# hextech-mechahand.net
KiCad netlist of a schematic drawn in EasyEDA
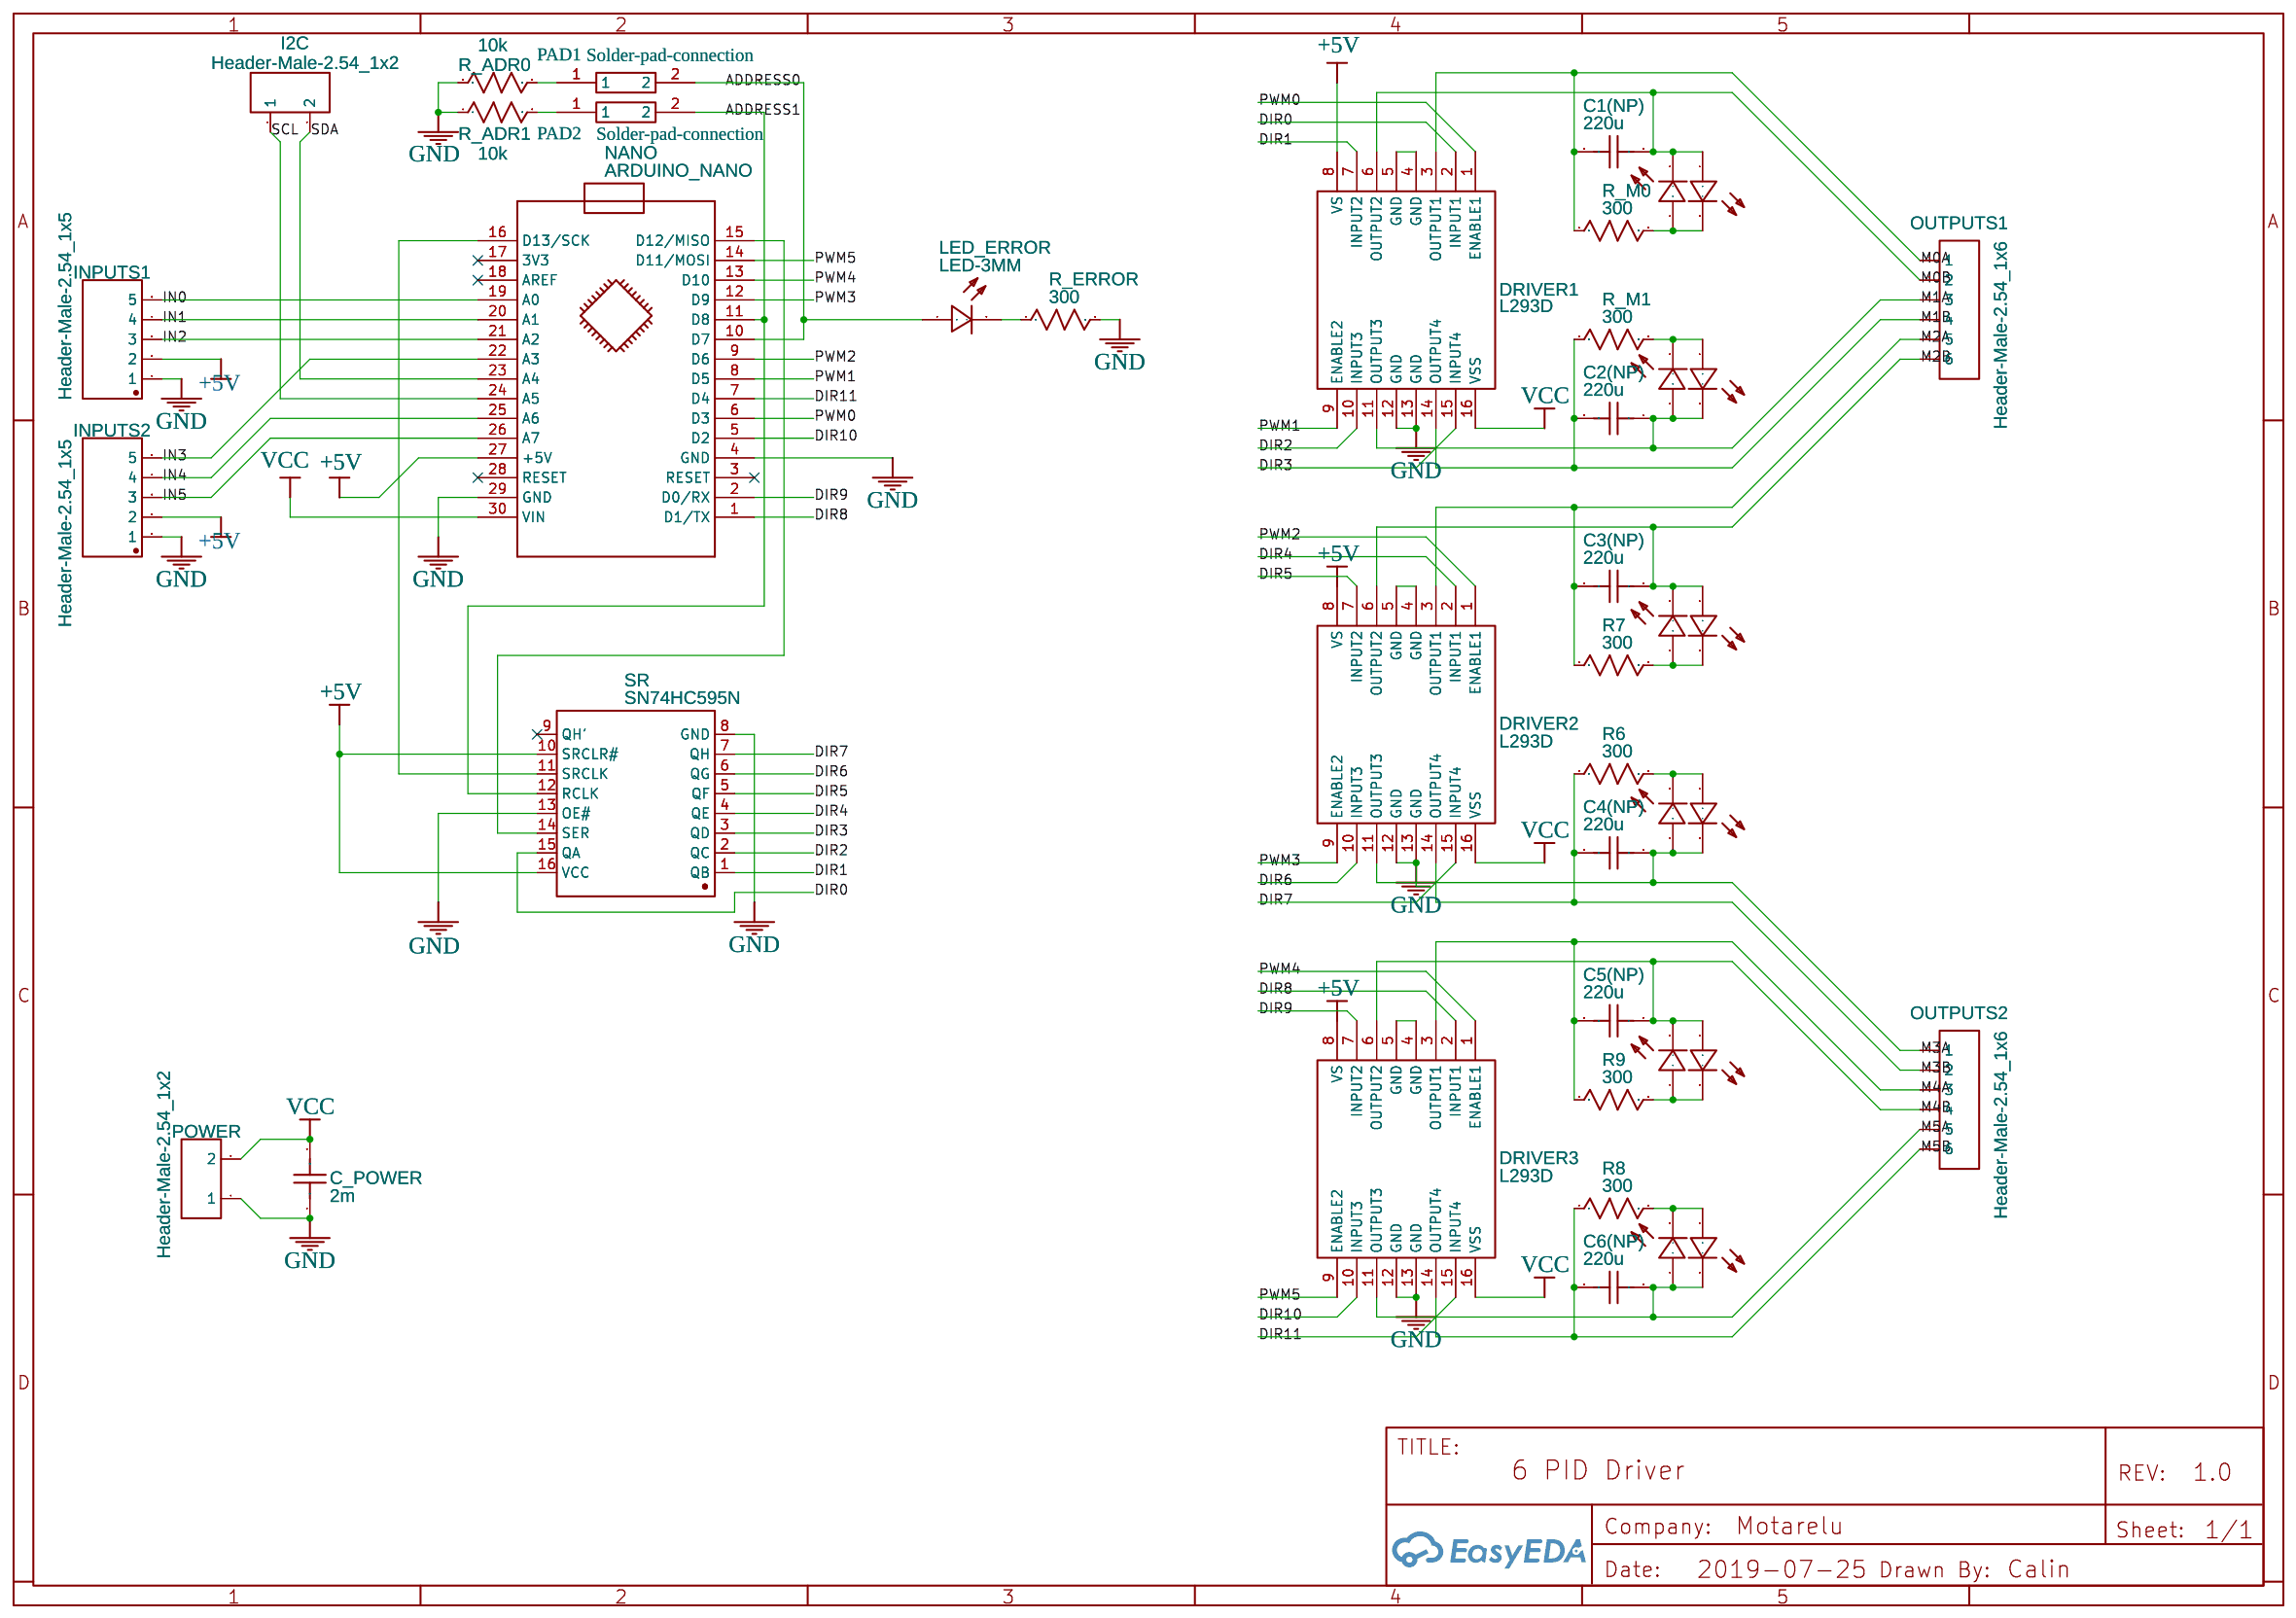
[diagram p0: schematic sheet]

(export (version "E")
  (design (tool "Eeschema 10.0.6"))
  (components
    (comp (ref "C1(NP)")
      (value "220u")
      (fields (field (name "BOM_Manufacturer Part") "?"))
      (libsource (lib "") (part "Cap_RAD-0.1_US_3"))
    )
    (comp (ref "C2(NP)")
      (value "220u")
      (fields (field (name "BOM_Manufacturer Part") "?"))
      (libsource (lib "") (part "Cap_RAD-0.1_US_5"))
    )
    (comp (ref "C3(NP)")
      (value "220u")
      (fields (field (name "BOM_Manufacturer Part") "?"))
      (libsource (lib "") (part "Cap_RAD-0.1_US"))
    )
    (comp (ref "C4(NP)")
      (value "220u")
      (fields (field (name "BOM_Manufacturer Part") "?"))
      (libsource (lib "") (part "Cap_RAD-0.1_US_2"))
    )
    (comp (ref "C5(NP)")
      (value "220u")
      (fields (field (name "BOM_Manufacturer Part") "?"))
      (libsource (lib "") (part "Cap_RAD-0.1_US_1"))
    )
    (comp (ref "C6(NP)")
      (value "220u")
      (fields (field (name "BOM_Manufacturer Part") "?"))
      (libsource (lib "") (part "Cap_RAD-0.1_US_6"))
    )
    (comp (ref "C_POWER")
      (value "2m")
      (fields (field (name "BOM_Manufacturer Part") "?"))
      (libsource (lib "") (part "Cap_RAD-0.1_US_4"))
    )
    (comp (ref "DRIVER1")
      (value "L293D")
      (fields (field (name "BOM_Supplier Part") "C12340"))
      (libsource (lib "") (part "Unknown_700_140"))
    )
    (comp (ref "DRIVER2")
      (value "L293D")
      (fields (field (name "BOM_Supplier Part") "C12340"))
      (libsource (lib "") (part "Unknown_700_360"))
    )
    (comp (ref "DRIVER3")
      (value "L293D")
      (fields (field (name "BOM_Supplier Part") "C12340"))
      (libsource (lib "") (part "Unknown_700_580"))
    )
    (comp (ref "I2C")
      (value "Header-Male-2.54_1x2")
      (fields (field (name "BOM_Manufacturer Part") "826629-2") (field (name "BOM_Supplier Part") "C86471"))
      (libsource (lib "") (part "Unknown_140_45"))
    )
    (comp (ref "INPUTS1")
      (value "Header-Male-2.54_1x5")
      (fields
        (field (name "BOM_Manufacturer Part") "210S-1*5P L=11.6MMGold-plated black")
        (field (name "BOM_Supplier Part") "C124379")
      )
      (libsource (lib "") (part "Unknown_55_165"))
    )
    (comp (ref "INPUTS2")
      (value "Header-Male-2.54_1x5")
      (fields
        (field (name "BOM_Manufacturer Part") "210S-1*5P L=11.6MMGold-plated black")
        (field (name "BOM_Supplier Part") "C124379")
      )
      (libsource (lib "") (part "Unknown_55_245"))
    )
    (comp (ref "LED_ERROR")
      (value "LED-3MM")
      (fields
        (field (name "BOM_Manufacturer Part") "204-10SURD/S530-A3")
        (field (name "BOM_Supplier Part") "C99772")
      )
      (libsource (lib "") (part "Unknown_480_150"))
    )
    (comp (ref "LED_M0A")
      (value "LED-3MM")
      (fields
        (field (name "BOM_Manufacturer Part") "204-10SURD/S530-A3")
        (field (name "BOM_Supplier Part") "C99772")
      )
      (libsource (lib "") (part "Unknown_835_90"))
    )
    (comp (ref "LED_M0B")
      (value "LED-3MM")
      (fields
        (field (name "BOM_Manufacturer Part") "204-10SURD/S530-A3")
        (field (name "BOM_Supplier Part") "C99772")
      )
      (libsource (lib "") (part "Unknown_860_90"))
    )
    (comp (ref "LED_M1A")
      (value "LED-3MM")
      (fields
        (field (name "BOM_Manufacturer Part") "204-10SURD/S530-A3")
        (field (name "BOM_Supplier Part") "C99772")
      )
      (libsource (lib "") (part "Unknown_835_185"))
    )
    (comp (ref "LED_M1B")
      (value "LED-3MM")
      (fields
        (field (name "BOM_Manufacturer Part") "204-10SURD/S530-A3")
        (field (name "BOM_Supplier Part") "C99772")
      )
      (libsource (lib "") (part "Unknown_860_185"))
    )
    (comp (ref "LED_M2A")
      (value "LED-3MM")
      (fields
        (field (name "BOM_Manufacturer Part") "204-10SURD/S530-A3")
        (field (name "BOM_Supplier Part") "C99772")
      )
      (libsource (lib "") (part "Unknown_835_310"))
    )
    (comp (ref "LED_M2B")
      (value "LED-3MM")
      (fields
        (field (name "BOM_Manufacturer Part") "204-10SURD/S530-A3")
        (field (name "BOM_Supplier Part") "C99772")
      )
      (libsource (lib "") (part "Unknown_860_310"))
    )
    (comp (ref "LED_M3A")
      (value "LED-3MM")
      (fields
        (field (name "BOM_Manufacturer Part") "204-10SURD/S530-A3")
        (field (name "BOM_Supplier Part") "C99772")
      )
      (libsource (lib "") (part "Unknown_835_405"))
    )
    (comp (ref "LED_M3B")
      (value "LED-3MM")
      (fields
        (field (name "BOM_Manufacturer Part") "204-10SURD/S530-A3")
        (field (name "BOM_Supplier Part") "C99772")
      )
      (libsource (lib "") (part "Unknown_860_405"))
    )
    (comp (ref "LED_M4A")
      (value "LED-3MM")
      (fields
        (field (name "BOM_Manufacturer Part") "204-10SURD/S530-A3")
        (field (name "BOM_Supplier Part") "C99772")
      )
      (libsource (lib "") (part "Unknown_835_530"))
    )
    (comp (ref "LED_M4B")
      (value "LED-3MM")
      (fields
        (field (name "BOM_Manufacturer Part") "204-10SURD/S530-A3")
        (field (name "BOM_Supplier Part") "C99772")
      )
      (libsource (lib "") (part "Unknown_860_530"))
    )
    (comp (ref "LED_M5A")
      (value "LED-3MM")
      (fields
        (field (name "BOM_Manufacturer Part") "204-10SURD/S530-A3")
        (field (name "BOM_Supplier Part") "C99772")
      )
      (libsource (lib "") (part "Unknown_835_625"))
    )
    (comp (ref "LED_M5B")
      (value "LED-3MM")
      (fields
        (field (name "BOM_Manufacturer Part") "204-10SURD/S530-A3")
        (field (name "BOM_Supplier Part") "C99772")
      )
      (libsource (lib "") (part "Unknown_860_625"))
    )
    (comp (ref "NANO")
      (value "ARDUINO_NANO")
      (fields (field (name "BOM_Manufacturer Part") "?"))
      (libsource (lib "") (part "Unknown_305_180"))
    )
    (comp (ref "OUTPUTS1")
      (value "Header-Male-2.54_1x6")
      (fields (field (name "BOM_Supplier Part") "C37208"))
      (libsource (lib "") (part "Unknown_980_150"))
    )
    (comp (ref "OUTPUTS2")
      (value "Header-Male-2.54_1x6")
      (fields (field (name "BOM_Supplier Part") "C37208"))
      (libsource (lib "") (part "Unknown_980_550"))
    )
    (comp (ref "PAD1") (value "Solder-pad-connection") (libsource (lib "") (part "Unknown_310_30")))
    (comp (ref "PAD2") (value "Solder-pad-connection") (libsource (lib "") (part "Unknown_310_45")))
    (comp (ref "POWER")
      (value "Header-Male-2.54_1x2")
      (fields (field (name "BOM_Manufacturer Part") "826629-2") (field (name "BOM_Supplier Part") "C86471"))
      (libsource (lib "") (part "Unknown_100_590"))
    )
    (comp (ref "R6")
      (value "300")
      (fields (field (name "BOM_Manufacturer Part") "?"))
      (libsource (lib "") (part "Res_AXIAL-0.3(1/8W)_US"))
    )
    (comp (ref "R7")
      (value "300")
      (fields (field (name "BOM_Manufacturer Part") "?"))
      (libsource (lib "") (part "Res_AXIAL-0.3(1/8W)_US"))
    )
    (comp (ref "R8")
      (value "300")
      (fields (field (name "BOM_Manufacturer Part") "?"))
      (libsource (lib "") (part "Res_AXIAL-0.3(1/8W)_US"))
    )
    (comp (ref "R9")
      (value "300")
      (fields (field (name "BOM_Manufacturer Part") "?"))
      (libsource (lib "") (part "Res_AXIAL-0.3(1/8W)_US"))
    )
    (comp (ref "R_ADR0")
      (value "10k")
      (fields (field (name "BOM_Manufacturer Part") "?"))
      (libsource (lib "") (part "Res_AXIAL-0.3(1/8W)_US_3"))
    )
    (comp (ref "R_ADR1")
      (value "10k")
      (fields (field (name "BOM_Manufacturer Part") "?"))
      (libsource (lib "") (part "Res_AXIAL-0.3(1/8W)_US_3"))
    )
    (comp (ref "R_ERROR")
      (value "300")
      (fields (field (name "BOM_Manufacturer Part") "?"))
      (libsource (lib "") (part "Res_AXIAL-0.3(1/8W)_US_1"))
    )
    (comp (ref "R_M0")
      (value "300")
      (fields (field (name "BOM_Manufacturer Part") "?"))
      (libsource (lib "") (part "Res_AXIAL-0.3(1/8W)_US_2"))
    )
    (comp (ref "R_M1")
      (value "300")
      (fields (field (name "BOM_Manufacturer Part") "?"))
      (libsource (lib "") (part "Res_AXIAL-0.3(1/8W)_US_2"))
    )
    (comp (ref "SR")
      (value "SN74HC595N")
      (fields (field (name "BOM_Supplier Part") "C78711"))
      (libsource (lib "") (part "Unknown_315_400"))
    )
  )
  (nets
    (net (code "1") (name "+5V") (class "Default")
      (node (ref "DRIVER1") (pin "8") (pinfunction "VS_8") (pintype "unspecified"))
      (node (ref "DRIVER2") (pin "8") (pinfunction "VS_8") (pintype "unspecified"))
      (node (ref "DRIVER3") (pin "8") (pinfunction "VS_8") (pintype "unspecified"))
      (node (ref "INPUTS1") (pin "2") (pinfunction "2_2") (pintype "unspecified"))
      (node (ref "INPUTS2") (pin "2") (pinfunction "2_2") (pintype "unspecified"))
      (node (ref "NANO") (pin "27") (pinfunction "+5V_27") (pintype "unspecified"))
      (node (ref "SR") (pin "10") (pinfunction "SRCLR#_10") (pintype "unspecified"))
      (node (ref "SR") (pin "16") (pinfunction "VCC_16") (pintype "unspecified"))
    )
    (net (code "2") (name "/ADDRESS0") (class "Default")
      (node (ref "LED_ERROR") (pin "1") (pinfunction "+_1") (pintype "unspecified"))
      (node (ref "NANO") (pin "10") (pinfunction "D7_10") (pintype "unspecified"))
      (node (ref "PAD1") (pin "2") (pinfunction "2_2") (pintype "unspecified"))
    )
    (net (code "3") (name "/ADDRESS1") (class "Default")
      (node (ref "NANO") (pin "11") (pinfunction "D8_11") (pintype "unspecified"))
      (node (ref "PAD2") (pin "2") (pinfunction "2_2") (pintype "unspecified"))
      (node (ref "SR") (pin "12") (pinfunction "RCLK_12") (pintype "unspecified"))
    )
    (net (code "4") (name "/DIR0") (class "Default")
      (node (ref "DRIVER1") (pin "2") (pinfunction "INPUT1_2") (pintype "unspecified"))
      (node (ref "SR") (pin "15") (pinfunction "QA_15") (pintype "unspecified"))
    )
    (net (code "5") (name "/DIR1") (class "Default")
      (node (ref "DRIVER1") (pin "7") (pinfunction "INPUT2_7") (pintype "unspecified"))
      (node (ref "SR") (pin "1") (pinfunction "QB_1") (pintype "unspecified"))
    )
    (net (code "6") (name "/DIR2") (class "Default")
      (node (ref "DRIVER1") (pin "10") (pinfunction "INPUT3_10") (pintype "unspecified"))
      (node (ref "SR") (pin "2") (pinfunction "QC_2") (pintype "unspecified"))
    )
    (net (code "7") (name "/DIR3") (class "Default")
      (node (ref "DRIVER1") (pin "15") (pinfunction "INPUT4_15") (pintype "unspecified"))
      (node (ref "SR") (pin "3") (pinfunction "QD_3") (pintype "unspecified"))
    )
    (net (code "8") (name "/DIR4") (class "Default")
      (node (ref "DRIVER2") (pin "2") (pinfunction "INPUT1_2") (pintype "unspecified"))
      (node (ref "SR") (pin "4") (pinfunction "QE_4") (pintype "unspecified"))
    )
    (net (code "9") (name "/DIR5") (class "Default")
      (node (ref "DRIVER2") (pin "7") (pinfunction "INPUT2_7") (pintype "unspecified"))
      (node (ref "SR") (pin "5") (pinfunction "QF_5") (pintype "unspecified"))
    )
    (net (code "10") (name "/DIR6") (class "Default")
      (node (ref "DRIVER2") (pin "10") (pinfunction "INPUT3_10") (pintype "unspecified"))
      (node (ref "SR") (pin "6") (pinfunction "QG_6") (pintype "unspecified"))
    )
    (net (code "11") (name "/DIR7") (class "Default")
      (node (ref "DRIVER2") (pin "15") (pinfunction "INPUT4_15") (pintype "unspecified"))
      (node (ref "SR") (pin "7") (pinfunction "QH_7") (pintype "unspecified"))
    )
    (net (code "12") (name "/DIR8") (class "Default")
      (node (ref "DRIVER3") (pin "2") (pinfunction "INPUT1_2") (pintype "unspecified"))
      (node (ref "NANO") (pin "1") (pinfunction "D1/TX_1") (pintype "unspecified"))
    )
    (net (code "13") (name "/DIR9") (class "Default")
      (node (ref "DRIVER3") (pin "7") (pinfunction "INPUT2_7") (pintype "unspecified"))
      (node (ref "NANO") (pin "2") (pinfunction "D0/RX_2") (pintype "unspecified"))
    )
    (net (code "14") (name "/DIR10") (class "Default")
      (node (ref "DRIVER3") (pin "10") (pinfunction "INPUT3_10") (pintype "unspecified"))
      (node (ref "NANO") (pin "5") (pinfunction "D2_5") (pintype "unspecified"))
    )
    (net (code "15") (name "/DIR11") (class "Default")
      (node (ref "DRIVER3") (pin "15") (pinfunction "INPUT4_15") (pintype "unspecified"))
      (node (ref "NANO") (pin "7") (pinfunction "D4_7") (pintype "unspecified"))
    )
    (net (code "16") (name "/IN0") (class "Default")
      (node (ref "INPUTS1") (pin "5") (pinfunction "5_5") (pintype "unspecified"))
      (node (ref "NANO") (pin "19") (pinfunction "A0_19") (pintype "unspecified"))
    )
    (net (code "17") (name "/IN1") (class "Default")
      (node (ref "INPUTS1") (pin "4") (pinfunction "4_4") (pintype "unspecified"))
      (node (ref "NANO") (pin "20") (pinfunction "A1_20") (pintype "unspecified"))
    )
    (net (code "18") (name "/IN2") (class "Default")
      (node (ref "INPUTS1") (pin "3") (pinfunction "3_3") (pintype "unspecified"))
      (node (ref "NANO") (pin "21") (pinfunction "A2_21") (pintype "unspecified"))
    )
    (net (code "19") (name "/IN3") (class "Default")
      (node (ref "INPUTS2") (pin "5") (pinfunction "5_5") (pintype "unspecified"))
      (node (ref "NANO") (pin "22") (pinfunction "A3_22") (pintype "unspecified"))
    )
    (net (code "20") (name "/IN4") (class "Default")
      (node (ref "INPUTS2") (pin "4") (pinfunction "4_4") (pintype "unspecified"))
      (node (ref "NANO") (pin "25") (pinfunction "A6_25") (pintype "unspecified"))
    )
    (net (code "21") (name "/IN5") (class "Default")
      (node (ref "INPUTS2") (pin "3") (pinfunction "3_3") (pintype "unspecified"))
      (node (ref "NANO") (pin "26") (pinfunction "A7_26") (pintype "unspecified"))
    )
    (net (code "22") (name "/M0A") (class "Default")
      (node (ref "C1(NP)") (pin "2") (pinfunction "2_2") (pintype "unspecified"))
      (node (ref "DRIVER1") (pin "3") (pinfunction "OUTPUT1_3") (pintype "unspecified"))
      (node (ref "OUTPUTS1") (pin "1") (pinfunction "1_1") (pintype "input"))
      (node (ref "R_M0") (pin "1") (pinfunction "1_1") (pintype "unspecified"))
    )
    (net (code "23") (name "/M0B") (class "Default")
      (node (ref "C1(NP)") (pin "1") (pinfunction "1_1") (pintype "unspecified"))
      (node (ref "DRIVER1") (pin "6") (pinfunction "OUTPUT2_6") (pintype "unspecified"))
      (node (ref "LED_M0A") (pin "2") (pinfunction "-_2") (pintype "unspecified"))
      (node (ref "LED_M0B") (pin "1") (pinfunction "+_1") (pintype "unspecified"))
      (node (ref "OUTPUTS1") (pin "2") (pinfunction "2_2") (pintype "input"))
    )
    (net (code "24") (name "/M1A") (class "Default")
      (node (ref "C2(NP)") (pin "1") (pinfunction "1_1") (pintype "unspecified"))
      (node (ref "DRIVER1") (pin "11") (pinfunction "OUTPUT3_11") (pintype "unspecified"))
      (node (ref "LED_M1A") (pin "1") (pinfunction "+_1") (pintype "unspecified"))
      (node (ref "LED_M1B") (pin "2") (pinfunction "-_2") (pintype "unspecified"))
      (node (ref "OUTPUTS1") (pin "3") (pinfunction "3_3") (pintype "input"))
    )
    (net (code "25") (name "/M1B") (class "Default")
      (node (ref "C2(NP)") (pin "2") (pinfunction "2_2") (pintype "unspecified"))
      (node (ref "DRIVER1") (pin "14") (pinfunction "OUTPUT4_14") (pintype "unspecified"))
      (node (ref "OUTPUTS1") (pin "4") (pinfunction "4_4") (pintype "input"))
      (node (ref "R_M1") (pin "1") (pinfunction "1_1") (pintype "unspecified"))
    )
    (net (code "26") (name "/M2A") (class "Default")
      (node (ref "C3(NP)") (pin "2") (pinfunction "2_2") (pintype "unspecified"))
      (node (ref "DRIVER2") (pin "3") (pinfunction "OUTPUT1_3") (pintype "unspecified"))
      (node (ref "OUTPUTS1") (pin "5") (pinfunction "5_5") (pintype "input"))
      (node (ref "R7") (pin "1") (pinfunction "1_1") (pintype "unspecified"))
    )
    (net (code "27") (name "/M2B") (class "Default")
      (node (ref "C3(NP)") (pin "1") (pinfunction "1_1") (pintype "unspecified"))
      (node (ref "DRIVER2") (pin "6") (pinfunction "OUTPUT2_6") (pintype "unspecified"))
      (node (ref "LED_M2A") (pin "2") (pinfunction "-_2") (pintype "unspecified"))
      (node (ref "LED_M2B") (pin "1") (pinfunction "+_1") (pintype "unspecified"))
      (node (ref "OUTPUTS1") (pin "6") (pinfunction "6_6") (pintype "input"))
    )
    (net (code "28") (name "/M3A") (class "Default")
      (node (ref "C4(NP)") (pin "1") (pinfunction "1_1") (pintype "unspecified"))
      (node (ref "DRIVER2") (pin "11") (pinfunction "OUTPUT3_11") (pintype "unspecified"))
      (node (ref "LED_M3A") (pin "1") (pinfunction "+_1") (pintype "unspecified"))
      (node (ref "LED_M3B") (pin "2") (pinfunction "-_2") (pintype "unspecified"))
      (node (ref "OUTPUTS2") (pin "1") (pinfunction "1_1") (pintype "input"))
    )
    (net (code "29") (name "/M3B") (class "Default")
      (node (ref "C4(NP)") (pin "2") (pinfunction "2_2") (pintype "unspecified"))
      (node (ref "DRIVER2") (pin "14") (pinfunction "OUTPUT4_14") (pintype "unspecified"))
      (node (ref "OUTPUTS2") (pin "2") (pinfunction "2_2") (pintype "input"))
      (node (ref "R6") (pin "1") (pinfunction "1_1") (pintype "unspecified"))
    )
    (net (code "30") (name "/M4A") (class "Default")
      (node (ref "C5(NP)") (pin "2") (pinfunction "2_2") (pintype "unspecified"))
      (node (ref "DRIVER3") (pin "3") (pinfunction "OUTPUT1_3") (pintype "unspecified"))
      (node (ref "OUTPUTS2") (pin "3") (pinfunction "3_3") (pintype "input"))
      (node (ref "R9") (pin "1") (pinfunction "1_1") (pintype "unspecified"))
    )
    (net (code "31") (name "/M4B") (class "Default")
      (node (ref "C5(NP)") (pin "1") (pinfunction "1_1") (pintype "unspecified"))
      (node (ref "DRIVER3") (pin "6") (pinfunction "OUTPUT2_6") (pintype "unspecified"))
      (node (ref "LED_M4A") (pin "2") (pinfunction "-_2") (pintype "unspecified"))
      (node (ref "LED_M4B") (pin "1") (pinfunction "+_1") (pintype "unspecified"))
      (node (ref "OUTPUTS2") (pin "4") (pinfunction "4_4") (pintype "input"))
    )
    (net (code "32") (name "/M5A") (class "Default")
      (node (ref "C6(NP)") (pin "1") (pinfunction "1_1") (pintype "unspecified"))
      (node (ref "DRIVER3") (pin "11") (pinfunction "OUTPUT3_11") (pintype "unspecified"))
      (node (ref "LED_M5A") (pin "1") (pinfunction "+_1") (pintype "unspecified"))
      (node (ref "LED_M5B") (pin "2") (pinfunction "-_2") (pintype "unspecified"))
      (node (ref "OUTPUTS2") (pin "5") (pinfunction "5_5") (pintype "input"))
    )
    (net (code "33") (name "/M5B") (class "Default")
      (node (ref "C6(NP)") (pin "2") (pinfunction "2_2") (pintype "unspecified"))
      (node (ref "DRIVER3") (pin "14") (pinfunction "OUTPUT4_14") (pintype "unspecified"))
      (node (ref "OUTPUTS2") (pin "6") (pinfunction "6_6") (pintype "input"))
      (node (ref "R8") (pin "1") (pinfunction "1_1") (pintype "unspecified"))
    )
    (net (code "34") (name "/PWM0") (class "Default")
      (node (ref "DRIVER1") (pin "1") (pinfunction "ENABLE1_1") (pintype "unspecified"))
      (node (ref "NANO") (pin "6") (pinfunction "D3_6") (pintype "unspecified"))
    )
    (net (code "35") (name "/PWM1") (class "Default")
      (node (ref "DRIVER1") (pin "9") (pinfunction "ENABLE2_9") (pintype "unspecified"))
      (node (ref "NANO") (pin "8") (pinfunction "D5_8") (pintype "unspecified"))
    )
    (net (code "36") (name "/PWM2") (class "Default")
      (node (ref "DRIVER2") (pin "1") (pinfunction "ENABLE1_1") (pintype "unspecified"))
      (node (ref "NANO") (pin "9") (pinfunction "D6_9") (pintype "unspecified"))
    )
    (net (code "37") (name "/PWM3") (class "Default")
      (node (ref "DRIVER2") (pin "9") (pinfunction "ENABLE2_9") (pintype "unspecified"))
      (node (ref "NANO") (pin "12") (pinfunction "D9_12") (pintype "unspecified"))
    )
    (net (code "38") (name "/PWM4") (class "Default")
      (node (ref "DRIVER3") (pin "1") (pinfunction "ENABLE1_1") (pintype "unspecified"))
      (node (ref "NANO") (pin "13") (pinfunction "D10_13") (pintype "unspecified"))
    )
    (net (code "39") (name "/PWM5") (class "Default")
      (node (ref "DRIVER3") (pin "9") (pinfunction "ENABLE2_9") (pintype "unspecified"))
      (node (ref "NANO") (pin "14") (pinfunction "D11/MOSI_14") (pintype "unspecified"))
    )
    (net (code "40") (name "/SCL") (class "Default")
      (node (ref "I2C") (pin "1") (pinfunction "1_1") (pintype "unspecified"))
      (node (ref "NANO") (pin "24") (pinfunction "A5_24") (pintype "unspecified"))
    )
    (net (code "41") (name "/SDA") (class "Default")
      (node (ref "I2C") (pin "2") (pinfunction "2_2") (pintype "unspecified"))
      (node (ref "NANO") (pin "23") (pinfunction "A4_23") (pintype "unspecified"))
    )
    (net (code "42") (name "GND") (class "Default")
      (node (ref "C_POWER") (pin "1") (pinfunction "1_1") (pintype "unspecified"))
      (node (ref "DRIVER1") (pin "12") (pinfunction "GND_12") (pintype "unspecified"))
      (node (ref "DRIVER1") (pin "13") (pinfunction "GND_13") (pintype "unspecified"))
      (node (ref "DRIVER2") (pin "12") (pinfunction "GND_12") (pintype "unspecified"))
      (node (ref "DRIVER2") (pin "13") (pinfunction "GND_13") (pintype "unspecified"))
      (node (ref "DRIVER3") (pin "12") (pinfunction "GND_12") (pintype "unspecified"))
      (node (ref "DRIVER3") (pin "13") (pinfunction "GND_13") (pintype "unspecified"))
      (node (ref "INPUTS1") (pin "1") (pinfunction "1_1") (pintype "unspecified"))
      (node (ref "INPUTS2") (pin "1") (pinfunction "1_1") (pintype "unspecified"))
      (node (ref "NANO") (pin "29") (pinfunction "GND_29") (pintype "unspecified"))
      (node (ref "NANO") (pin "4") (pinfunction "GND_4") (pintype "unspecified"))
      (node (ref "POWER") (pin "1") (pinfunction "1_1") (pintype "unspecified"))
      (node (ref "R_ADR0") (pin "1") (pinfunction "1_1") (pintype "unspecified"))
      (node (ref "R_ADR1") (pin "1") (pinfunction "1_1") (pintype "unspecified"))
      (node (ref "R_ERROR") (pin "2") (pinfunction "2_2") (pintype "unspecified"))
      (node (ref "SR") (pin "13") (pinfunction "OE#_13") (pintype "unspecified"))
      (node (ref "SR") (pin "8") (pinfunction "GND_8") (pintype "unspecified"))
    )
    (net (code "43") (name "Net-(DRIVER1-GND-Pad4)") (class "Default")
      (node (ref "DRIVER1") (pin "4") (pinfunction "GND_4") (pintype "unspecified"))
      (node (ref "DRIVER1") (pin "5") (pinfunction "GND_5") (pintype "unspecified"))
    )
    (net (code "44") (name "Net-(DRIVER2-GND-Pad4)") (class "Default")
      (node (ref "DRIVER2") (pin "4") (pinfunction "GND_4") (pintype "unspecified"))
      (node (ref "DRIVER2") (pin "5") (pinfunction "GND_5") (pintype "unspecified"))
    )
    (net (code "45") (name "Net-(DRIVER3-GND-Pad4)") (class "Default")
      (node (ref "DRIVER3") (pin "4") (pinfunction "GND_4") (pintype "unspecified"))
      (node (ref "DRIVER3") (pin "5") (pinfunction "GND_5") (pintype "unspecified"))
    )
    (net (code "46") (name "Net-(LED_ERROR--)") (class "Default")
      (node (ref "LED_ERROR") (pin "2") (pinfunction "-_2") (pintype "unspecified"))
      (node (ref "R_ERROR") (pin "1") (pinfunction "1_1") (pintype "unspecified"))
    )
    (net (code "47") (name "Net-(LED_M0A-+)") (class "Default")
      (node (ref "LED_M0A") (pin "1") (pinfunction "+_1") (pintype "unspecified"))
      (node (ref "LED_M0B") (pin "2") (pinfunction "-_2") (pintype "unspecified"))
      (node (ref "R_M0") (pin "2") (pinfunction "2_2") (pintype "unspecified"))
    )
    (net (code "48") (name "Net-(LED_M1A--)") (class "Default")
      (node (ref "LED_M1A") (pin "2") (pinfunction "-_2") (pintype "unspecified"))
      (node (ref "LED_M1B") (pin "1") (pinfunction "+_1") (pintype "unspecified"))
      (node (ref "R_M1") (pin "2") (pinfunction "2_2") (pintype "unspecified"))
    )
    (net (code "49") (name "Net-(LED_M2A-+)") (class "Default")
      (node (ref "LED_M2A") (pin "1") (pinfunction "+_1") (pintype "unspecified"))
      (node (ref "LED_M2B") (pin "2") (pinfunction "-_2") (pintype "unspecified"))
      (node (ref "R7") (pin "2") (pinfunction "2_2") (pintype "unspecified"))
    )
    (net (code "50") (name "Net-(LED_M3A--)") (class "Default")
      (node (ref "LED_M3A") (pin "2") (pinfunction "-_2") (pintype "unspecified"))
      (node (ref "LED_M3B") (pin "1") (pinfunction "+_1") (pintype "unspecified"))
      (node (ref "R6") (pin "2") (pinfunction "2_2") (pintype "unspecified"))
    )
    (net (code "51") (name "Net-(LED_M4A-+)") (class "Default")
      (node (ref "LED_M4A") (pin "1") (pinfunction "+_1") (pintype "unspecified"))
      (node (ref "LED_M4B") (pin "2") (pinfunction "-_2") (pintype "unspecified"))
      (node (ref "R9") (pin "2") (pinfunction "2_2") (pintype "unspecified"))
    )
    (net (code "52") (name "Net-(LED_M5A--)") (class "Default")
      (node (ref "LED_M5A") (pin "2") (pinfunction "-_2") (pintype "unspecified"))
      (node (ref "LED_M5B") (pin "1") (pinfunction "+_1") (pintype "unspecified"))
      (node (ref "R8") (pin "2") (pinfunction "2_2") (pintype "unspecified"))
    )
    (net (code "53") (name "Net-(NANO-D12{slash}MISO)") (class "Default")
      (node (ref "NANO") (pin "15") (pinfunction "D12/MISO_15") (pintype "unspecified"))
      (node (ref "SR") (pin "14") (pinfunction "SER_14") (pintype "unspecified"))
    )
    (net (code "54") (name "Net-(NANO-D13{slash}SCK)") (class "Default")
      (node (ref "NANO") (pin "16") (pinfunction "D13/SCK_16") (pintype "unspecified"))
      (node (ref "SR") (pin "11") (pinfunction "SRCLK_11") (pintype "unspecified"))
    )
    (net (code "55") (name "Net-(PAD1-Pad1)") (class "Default")
      (node (ref "PAD1") (pin "1") (pinfunction "1_1") (pintype "unspecified"))
      (node (ref "R_ADR0") (pin "2") (pinfunction "2_2") (pintype "unspecified"))
    )
    (net (code "56") (name "Net-(PAD2-Pad1)") (class "Default")
      (node (ref "PAD2") (pin "1") (pinfunction "1_1") (pintype "unspecified"))
      (node (ref "R_ADR1") (pin "2") (pinfunction "2_2") (pintype "unspecified"))
    )
    (net (code "57") (name "VCC") (class "Default")
      (node (ref "C_POWER") (pin "2") (pinfunction "2_2") (pintype "unspecified"))
      (node (ref "DRIVER1") (pin "16") (pinfunction "VSS_16") (pintype "unspecified"))
      (node (ref "DRIVER2") (pin "16") (pinfunction "VSS_16") (pintype "unspecified"))
      (node (ref "DRIVER3") (pin "16") (pinfunction "VSS_16") (pintype "unspecified"))
      (node (ref "NANO") (pin "30") (pinfunction "VIN_30") (pintype "unspecified"))
      (node (ref "POWER") (pin "2") (pinfunction "2_2") (pintype "unspecified"))
    )
    (net (code "58") (name "unconnected-(NANO-3V3-Pad17)") (class "Default")
      (node (ref "NANO") (pin "17") (pinfunction "3V3_17") (pintype "unspecified+no_connect"))
    )
    (net (code "59") (name "unconnected-(NANO-AREF-Pad18)") (class "Default")
      (node (ref "NANO") (pin "18") (pinfunction "AREF_18") (pintype "unspecified+no_connect"))
    )
    (net (code "60") (name "unconnected-(NANO-RESET-Pad3)") (class "Default")
      (node (ref "NANO") (pin "3") (pinfunction "RESET_3") (pintype "unspecified+no_connect"))
    )
    (net (code "61") (name "unconnected-(NANO-RESET-Pad28)") (class "Default")
      (node (ref "NANO") (pin "28") (pinfunction "RESET_28") (pintype "unspecified+no_connect"))
    )
    (net (code "62") (name "unconnected-(SR-QH'-Pad9)") (class "Default")
      (node (ref "SR") (pin "9") (pinfunction "QH'_9") (pintype "unspecified+no_connect"))
    )
  )
)
